# tone.net
KiCad netlist of a schematic drawn in EAGLE
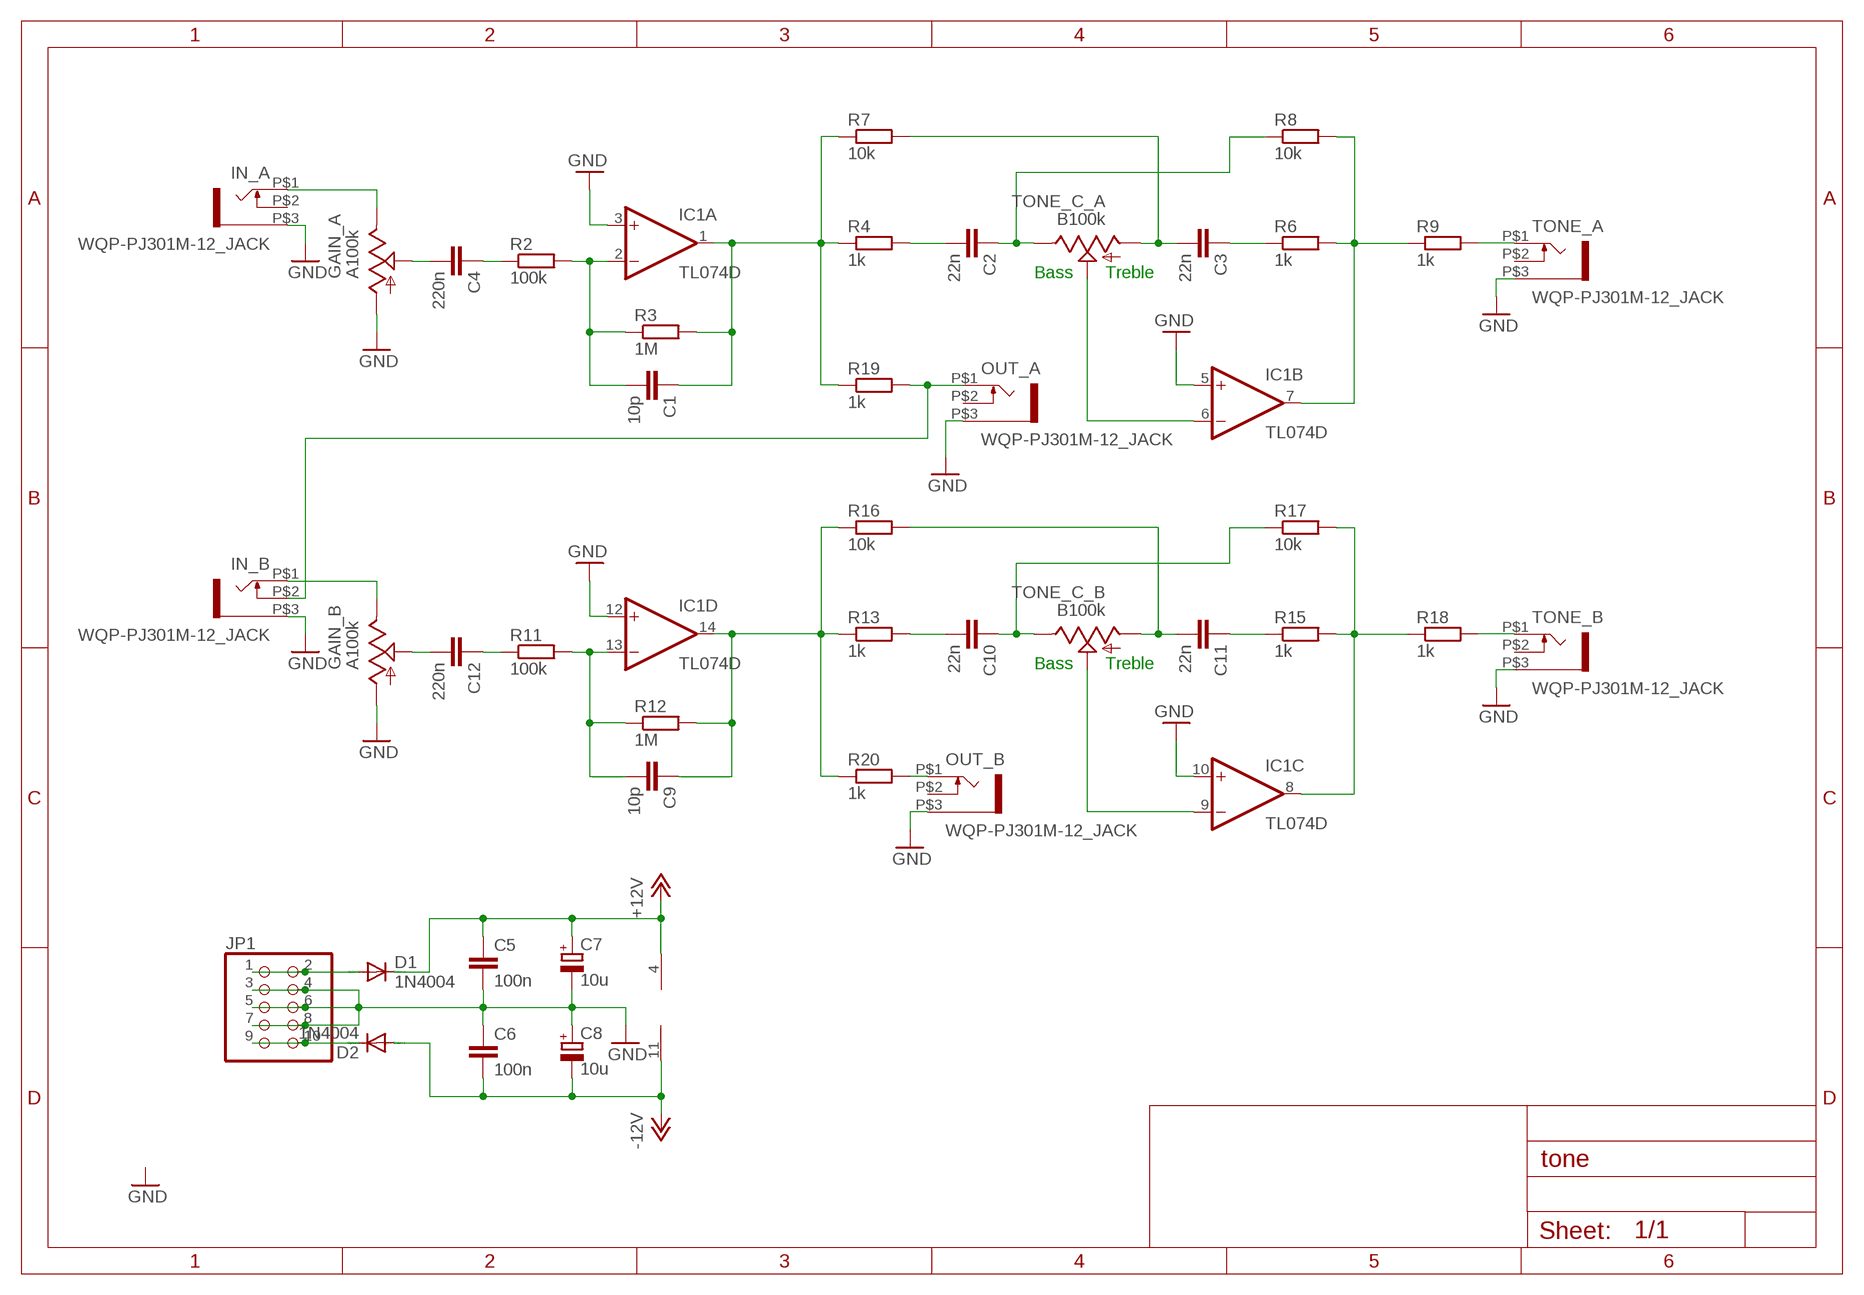
[diagram p0: schematic, sheet 1]

(export (version "E")
  (design (tool "Eeschema 10.0.6"))
  (components
    (comp (ref "C1")
      (value "10p")
      (footprint "eagle-import:C0603K")
      (libsource (lib "eagle-import") (part "C-EUC0603K"))
    )
    (comp (ref "C2")
      (value "22n")
      (footprint "eagle-import:C050-025X075")
      (libsource (lib "eagle-import") (part "C-EU050-025X075"))
    )
    (comp (ref "C3")
      (value "22n")
      (footprint "eagle-import:C050-025X075")
      (libsource (lib "eagle-import") (part "C-EU050-025X075"))
    )
    (comp (ref "C4")
      (value "220n")
      (footprint "eagle-import:C050-025X075")
      (libsource (lib "eagle-import") (part "C-EU050-025X075"))
    )
    (comp (ref "C5")
      (value "100n")
      (footprint "eagle-import:C025-025X050")
      (libsource (lib "eagle-import") (part "C-EU025-025X050"))
    )
    (comp (ref "C6")
      (value "100n")
      (footprint "eagle-import:C025-025X050")
      (libsource (lib "eagle-import") (part "C-EU025-025X050"))
    )
    (comp (ref "C7")
      (value "10u")
      (footprint "eagle-import:E2,5-6")
      (libsource (lib "eagle-import") (part "CPOL-EUE2.5-6"))
    )
    (comp (ref "C8")
      (value "10u")
      (footprint "eagle-import:E2,5-6")
      (libsource (lib "eagle-import") (part "CPOL-EUE2.5-6"))
    )
    (comp (ref "C9")
      (value "10p")
      (footprint "eagle-import:C0603K")
      (libsource (lib "eagle-import") (part "C-EUC0603K"))
    )
    (comp (ref "C10")
      (value "22n")
      (footprint "eagle-import:C050-025X075")
      (libsource (lib "eagle-import") (part "C-EU050-025X075"))
    )
    (comp (ref "C11")
      (value "22n")
      (footprint "eagle-import:C050-025X075")
      (libsource (lib "eagle-import") (part "C-EU050-025X075"))
    )
    (comp (ref "C12")
      (value "220n")
      (footprint "eagle-import:C050-025X075")
      (libsource (lib "eagle-import") (part "C-EU050-025X075"))
    )
    (comp (ref "D1")
      (value "1N4004")
      (footprint "eagle-import:DO41-10")
      (libsource (lib "eagle-import") (part "1N4004"))
    )
    (comp (ref "D2")
      (value "1N4004")
      (footprint "eagle-import:DO41-10")
      (libsource (lib "eagle-import") (part "1N4004"))
    )
    (comp (ref "GAIN_A")
      (value "A100k")
      (footprint "eagle-import:ALPS_POT_VERTICAL")
      (libsource (lib "eagle-import") (part "POT_USVERTICAL"))
    )
    (comp (ref "GAIN_B")
      (value "A100k")
      (footprint "eagle-import:ALPS_POT_VERTICAL")
      (libsource (lib "eagle-import") (part "POT_USVERTICAL"))
    )
    (comp (ref "IC1")
      (value "TL074D")
      (footprint "eagle-import:SO14")
      (libsource (lib "eagle-import") (part "TL074D"))
    )
    (comp (ref "IN_A")
      (value "WQP-PJ301M-12_JACK")
      (footprint "eagle-import:WQP-PJ301M-12_JACK")
      (libsource (lib "eagle-import") (part "WQP-PJ301M-12_JACK"))
    )
    (comp (ref "IN_B")
      (value "WQP-PJ301M-12_JACK")
      (footprint "eagle-import:WQP-PJ301M-12_JACK")
      (libsource (lib "eagle-import") (part "WQP-PJ301M-12_JACK"))
    )
    (comp (ref "JP1")
      (value "PINHD-2X5")
      (footprint "eagle-import:2X05")
      (libsource (lib "eagle-import") (part "PINHD-2X5"))
    )
    (comp (ref "OUT_A")
      (value "WQP-PJ301M-12_JACK")
      (footprint "eagle-import:WQP-PJ301M-12_JACK")
      (libsource (lib "eagle-import") (part "WQP-PJ301M-12_JACK"))
    )
    (comp (ref "OUT_B")
      (value "WQP-PJ301M-12_JACK")
      (footprint "eagle-import:WQP-PJ301M-12_JACK")
      (libsource (lib "eagle-import") (part "WQP-PJ301M-12_JACK"))
    )
    (comp (ref "R2")
      (value "100k")
      (footprint "eagle-import:R0603")
      (libsource (lib "eagle-import") (part "R-EU_R0603"))
    )
    (comp (ref "R3")
      (value "1M")
      (footprint "eagle-import:R0603")
      (libsource (lib "eagle-import") (part "R-EU_R0603"))
    )
    (comp (ref "R4")
      (value "1k")
      (footprint "eagle-import:R0603")
      (libsource (lib "eagle-import") (part "R-EU_R0603"))
    )
    (comp (ref "R6")
      (value "1k")
      (footprint "eagle-import:R0603")
      (libsource (lib "eagle-import") (part "R-EU_R0603"))
    )
    (comp (ref "R7")
      (value "10k")
      (footprint "eagle-import:R0603")
      (libsource (lib "eagle-import") (part "R-EU_R0603"))
    )
    (comp (ref "R8")
      (value "10k")
      (footprint "eagle-import:R0603")
      (libsource (lib "eagle-import") (part "R-EU_R0603"))
    )
    (comp (ref "R9")
      (value "1k")
      (footprint "eagle-import:R0603")
      (libsource (lib "eagle-import") (part "R-EU_R0603"))
    )
    (comp (ref "R11")
      (value "100k")
      (footprint "eagle-import:R0603")
      (libsource (lib "eagle-import") (part "R-EU_R0603"))
    )
    (comp (ref "R12")
      (value "1M")
      (footprint "eagle-import:R0603")
      (libsource (lib "eagle-import") (part "R-EU_R0603"))
    )
    (comp (ref "R13")
      (value "1k")
      (footprint "eagle-import:R0603")
      (libsource (lib "eagle-import") (part "R-EU_R0603"))
    )
    (comp (ref "R15")
      (value "1k")
      (footprint "eagle-import:R0603")
      (libsource (lib "eagle-import") (part "R-EU_R0603"))
    )
    (comp (ref "R16")
      (value "10k")
      (footprint "eagle-import:R0603")
      (libsource (lib "eagle-import") (part "R-EU_R0603"))
    )
    (comp (ref "R17")
      (value "10k")
      (footprint "eagle-import:R0603")
      (libsource (lib "eagle-import") (part "R-EU_R0603"))
    )
    (comp (ref "R18")
      (value "1k")
      (footprint "eagle-import:R0603")
      (libsource (lib "eagle-import") (part "R-EU_R0603"))
    )
    (comp (ref "R19")
      (value "1k")
      (footprint "eagle-import:R0603")
      (libsource (lib "eagle-import") (part "R-EU_R0603"))
    )
    (comp (ref "R20")
      (value "1k")
      (footprint "eagle-import:R0603")
      (libsource (lib "eagle-import") (part "R-EU_R0603"))
    )
    (comp (ref "TONE_A")
      (value "WQP-PJ301M-12_JACK")
      (footprint "eagle-import:WQP-PJ301M-12_JACK")
      (libsource (lib "eagle-import") (part "WQP-PJ301M-12_JACK"))
    )
    (comp (ref "TONE_B")
      (value "WQP-PJ301M-12_JACK")
      (footprint "eagle-import:WQP-PJ301M-12_JACK")
      (libsource (lib "eagle-import") (part "WQP-PJ301M-12_JACK"))
    )
    (comp (ref "TONE_C_A")
      (value "B100k")
      (footprint "eagle-import:ALPS_POT_VERTICAL")
      (libsource (lib "eagle-import") (part "POT_USVERTICAL"))
    )
    (comp (ref "TONE_C_B")
      (value "B100k")
      (footprint "eagle-import:ALPS_POT_VERTICAL")
      (libsource (lib "eagle-import") (part "POT_USVERTICAL"))
    )
  )
  (nets
    (net (code "1") (name "+12V") (class "Default")
      (node (ref "C5") (pin "1") (pinfunction "1_1") (pintype "passive"))
      (node (ref "C7") (pin "+") (pinfunction "+_+") (pintype "passive"))
      (node (ref "D1") (pin "C") (pinfunction "C_C") (pintype "passive"))
      (node (ref "IC1") (pin "4") (pinfunction "V+_4") (pintype "power_in"))
    )
    (net (code "2") (name "-12V") (class "Default")
      (node (ref "C6") (pin "2") (pinfunction "2_2") (pintype "passive"))
      (node (ref "C8") (pin "-") (pinfunction "-_-") (pintype "passive"))
      (node (ref "D2") (pin "A") (pinfunction "A_A") (pintype "passive"))
      (node (ref "IC1") (pin "11") (pinfunction "V-_11") (pintype "power_in"))
    )
    (net (code "3") (name "GND") (class "Default")
      (node (ref "C5") (pin "2") (pinfunction "2_2") (pintype "passive"))
      (node (ref "C6") (pin "1") (pinfunction "1_1") (pintype "passive"))
      (node (ref "C7") (pin "-") (pinfunction "-_-") (pintype "passive"))
      (node (ref "C8") (pin "+") (pinfunction "+_+") (pintype "passive"))
      (node (ref "GAIN_A") (pin "P$3") (pinfunction "A_P$3") (pintype "passive"))
      (node (ref "GAIN_B") (pin "P$3") (pinfunction "A_P$3") (pintype "passive"))
      (node (ref "IC1") (pin "10") (pinfunction "+IN_10") (pintype "input"))
      (node (ref "IC1") (pin "12") (pinfunction "+IN_12") (pintype "input"))
      (node (ref "IC1") (pin "3") (pinfunction "+IN_3") (pintype "input"))
      (node (ref "IC1") (pin "5") (pinfunction "+IN_5") (pintype "input"))
      (node (ref "IN_A") (pin "P$3") (pinfunction "1_P$3") (pintype "passive"))
      (node (ref "IN_B") (pin "P$3") (pinfunction "1_P$3") (pintype "passive"))
      (node (ref "JP1") (pin "3") (pinfunction "3_3") (pintype "passive"))
      (node (ref "JP1") (pin "4") (pinfunction "4_4") (pintype "passive"))
      (node (ref "JP1") (pin "5") (pinfunction "5_5") (pintype "passive"))
      (node (ref "JP1") (pin "6") (pinfunction "6_6") (pintype "passive"))
      (node (ref "JP1") (pin "7") (pinfunction "7_7") (pintype "passive"))
      (node (ref "JP1") (pin "8") (pinfunction "8_8") (pintype "passive"))
      (node (ref "OUT_A") (pin "P$3") (pinfunction "1_P$3") (pintype "passive"))
      (node (ref "OUT_B") (pin "P$3") (pinfunction "1_P$3") (pintype "passive"))
      (node (ref "TONE_A") (pin "P$3") (pinfunction "1_P$3") (pintype "passive"))
      (node (ref "TONE_B") (pin "P$3") (pinfunction "1_P$3") (pintype "passive"))
    )
    (net (code "4") (name "Net-(C2-Pad2)") (class "Default")
      (node (ref "C2") (pin "2") (pinfunction "2_2") (pintype "passive"))
      (node (ref "R4") (pin "2") (pinfunction "2_2") (pintype "passive"))
    )
    (net (code "5") (name "Net-(C3-Pad1)") (class "Default")
      (node (ref "C3") (pin "1") (pinfunction "1_1") (pintype "passive"))
      (node (ref "R6") (pin "1") (pinfunction "1_1") (pintype "passive"))
    )
    (net (code "6") (name "Net-(C4-Pad1)") (class "Default")
      (node (ref "C4") (pin "1") (pinfunction "1_1") (pintype "passive"))
      (node (ref "R2") (pin "1") (pinfunction "1_1") (pintype "passive"))
    )
    (net (code "7") (name "Net-(C10-Pad2)") (class "Default")
      (node (ref "C10") (pin "2") (pinfunction "2_2") (pintype "passive"))
      (node (ref "R13") (pin "2") (pinfunction "2_2") (pintype "passive"))
    )
    (net (code "8") (name "Net-(C11-Pad1)") (class "Default")
      (node (ref "C11") (pin "1") (pinfunction "1_1") (pintype "passive"))
      (node (ref "R15") (pin "1") (pinfunction "1_1") (pintype "passive"))
    )
    (net (code "9") (name "Net-(C12-Pad1)") (class "Default")
      (node (ref "C12") (pin "1") (pinfunction "1_1") (pintype "passive"))
      (node (ref "R11") (pin "1") (pinfunction "1_1") (pintype "passive"))
    )
    (net (code "10") (name "Net-(D1-PadA)") (class "Default")
      (node (ref "D1") (pin "A") (pinfunction "A_A") (pintype "passive"))
      (node (ref "JP1") (pin "1") (pinfunction "1_1") (pintype "passive"))
      (node (ref "JP1") (pin "2") (pinfunction "2_2") (pintype "passive"))
    )
    (net (code "11") (name "Net-(D2-PadC)") (class "Default")
      (node (ref "D2") (pin "C") (pinfunction "C_C") (pintype "passive"))
      (node (ref "JP1") (pin "10") (pinfunction "10_10") (pintype "passive"))
      (node (ref "JP1") (pin "9") (pinfunction "9_9") (pintype "passive"))
    )
    (net (code "12") (name "Net-(GAIN_A-E)") (class "Default")
      (node (ref "GAIN_A") (pin "P$1") (pinfunction "E_P$1") (pintype "passive"))
      (node (ref "IN_A") (pin "P$1") (pinfunction "2_P$1") (pintype "passive"))
    )
    (net (code "13") (name "Net-(GAIN_A-S)") (class "Default")
      (node (ref "C4") (pin "2") (pinfunction "2_2") (pintype "passive"))
      (node (ref "GAIN_A") (pin "P$2") (pinfunction "S_P$2") (pintype "passive"))
    )
    (net (code "14") (name "Net-(GAIN_B-E)") (class "Default")
      (node (ref "GAIN_B") (pin "P$1") (pinfunction "E_P$1") (pintype "passive"))
      (node (ref "IN_B") (pin "P$1") (pinfunction "2_P$1") (pintype "passive"))
    )
    (net (code "15") (name "Net-(GAIN_B-S)") (class "Default")
      (node (ref "C12") (pin "2") (pinfunction "2_2") (pintype "passive"))
      (node (ref "GAIN_B") (pin "P$2") (pinfunction "S_P$2") (pintype "passive"))
    )
    (net (code "16") (name "Net-(IC1A--IN)") (class "Default")
      (node (ref "C1") (pin "2") (pinfunction "2_2") (pintype "passive"))
      (node (ref "IC1") (pin "2") (pinfunction "-IN_2") (pintype "input"))
      (node (ref "R2") (pin "2") (pinfunction "2_2") (pintype "passive"))
      (node (ref "R3") (pin "1") (pinfunction "1_1") (pintype "passive"))
    )
    (net (code "17") (name "Net-(IC1A-OUT)") (class "Default")
      (node (ref "C1") (pin "1") (pinfunction "1_1") (pintype "passive"))
      (node (ref "IC1") (pin "1") (pinfunction "OUT_1") (pintype "output"))
      (node (ref "R19") (pin "1") (pinfunction "1_1") (pintype "passive"))
      (node (ref "R3") (pin "2") (pinfunction "2_2") (pintype "passive"))
      (node (ref "R4") (pin "1") (pinfunction "1_1") (pintype "passive"))
      (node (ref "R7") (pin "1") (pinfunction "1_1") (pintype "passive"))
    )
    (net (code "18") (name "Net-(IC1B--IN)") (class "Default")
      (node (ref "IC1") (pin "6") (pinfunction "-IN_6") (pintype "input"))
      (node (ref "TONE_C_A") (pin "P$2") (pinfunction "S_P$2") (pintype "passive"))
    )
    (net (code "19") (name "Net-(IC1B-OUT)") (class "Default")
      (node (ref "IC1") (pin "7") (pinfunction "OUT_7") (pintype "output"))
      (node (ref "R6") (pin "2") (pinfunction "2_2") (pintype "passive"))
      (node (ref "R8") (pin "2") (pinfunction "2_2") (pintype "passive"))
      (node (ref "R9") (pin "1") (pinfunction "1_1") (pintype "passive"))
    )
    (net (code "20") (name "Net-(IC1C--IN)") (class "Default")
      (node (ref "IC1") (pin "9") (pinfunction "-IN_9") (pintype "input"))
      (node (ref "TONE_C_B") (pin "P$2") (pinfunction "S_P$2") (pintype "passive"))
    )
    (net (code "21") (name "Net-(IC1C-OUT)") (class "Default")
      (node (ref "IC1") (pin "8") (pinfunction "OUT_8") (pintype "output"))
      (node (ref "R15") (pin "2") (pinfunction "2_2") (pintype "passive"))
      (node (ref "R17") (pin "2") (pinfunction "2_2") (pintype "passive"))
      (node (ref "R18") (pin "1") (pinfunction "1_1") (pintype "passive"))
    )
    (net (code "22") (name "Net-(IC1D--IN)") (class "Default")
      (node (ref "C9") (pin "2") (pinfunction "2_2") (pintype "passive"))
      (node (ref "IC1") (pin "13") (pinfunction "-IN_13") (pintype "input"))
      (node (ref "R11") (pin "2") (pinfunction "2_2") (pintype "passive"))
      (node (ref "R12") (pin "1") (pinfunction "1_1") (pintype "passive"))
    )
    (net (code "23") (name "Net-(IC1D-OUT)") (class "Default")
      (node (ref "C9") (pin "1") (pinfunction "1_1") (pintype "passive"))
      (node (ref "IC1") (pin "14") (pinfunction "OUT_14") (pintype "output"))
      (node (ref "R12") (pin "2") (pinfunction "2_2") (pintype "passive"))
      (node (ref "R13") (pin "1") (pinfunction "1_1") (pintype "passive"))
      (node (ref "R16") (pin "1") (pinfunction "1_1") (pintype "passive"))
      (node (ref "R20") (pin "1") (pinfunction "1_1") (pintype "passive"))
    )
    (net (code "24") (name "Net-(IN_B-3)") (class "Default")
      (node (ref "IN_B") (pin "P$2") (pinfunction "3_P$2") (pintype "passive"))
      (node (ref "OUT_A") (pin "P$1") (pinfunction "2_P$1") (pintype "passive"))
      (node (ref "R19") (pin "2") (pinfunction "2_2") (pintype "passive"))
    )
    (net (code "25") (name "Net-(OUT_B-2)") (class "Default")
      (node (ref "OUT_B") (pin "P$1") (pinfunction "2_P$1") (pintype "passive"))
      (node (ref "R20") (pin "2") (pinfunction "2_2") (pintype "passive"))
    )
    (net (code "26") (name "Net-(TONE_A-2)") (class "Default")
      (node (ref "R9") (pin "2") (pinfunction "2_2") (pintype "passive"))
      (node (ref "TONE_A") (pin "P$1") (pinfunction "2_P$1") (pintype "passive"))
    )
    (net (code "27") (name "Net-(TONE_B-2)") (class "Default")
      (node (ref "R18") (pin "2") (pinfunction "2_2") (pintype "passive"))
      (node (ref "TONE_B") (pin "P$1") (pinfunction "2_P$1") (pintype "passive"))
    )
    (net (code "28") (name "Net-(TONE_C_A-A)") (class "Default")
      (node (ref "C3") (pin "2") (pinfunction "2_2") (pintype "passive"))
      (node (ref "R7") (pin "2") (pinfunction "2_2") (pintype "passive"))
      (node (ref "TONE_C_A") (pin "P$3") (pinfunction "A_P$3") (pintype "passive"))
    )
    (net (code "29") (name "Net-(TONE_C_A-E)") (class "Default")
      (node (ref "C2") (pin "1") (pinfunction "1_1") (pintype "passive"))
      (node (ref "R8") (pin "1") (pinfunction "1_1") (pintype "passive"))
      (node (ref "TONE_C_A") (pin "P$1") (pinfunction "E_P$1") (pintype "passive"))
    )
    (net (code "30") (name "Net-(TONE_C_B-A)") (class "Default")
      (node (ref "C11") (pin "2") (pinfunction "2_2") (pintype "passive"))
      (node (ref "R16") (pin "2") (pinfunction "2_2") (pintype "passive"))
      (node (ref "TONE_C_B") (pin "P$3") (pinfunction "A_P$3") (pintype "passive"))
    )
    (net (code "31") (name "Net-(TONE_C_B-E)") (class "Default")
      (node (ref "C10") (pin "1") (pinfunction "1_1") (pintype "passive"))
      (node (ref "R17") (pin "1") (pinfunction "1_1") (pintype "passive"))
      (node (ref "TONE_C_B") (pin "P$1") (pinfunction "E_P$1") (pintype "passive"))
    )
    (net (code "32") (name "unconnected-(IN_A-3-PadP$2)") (class "Default")
      (node (ref "IN_A") (pin "P$2") (pinfunction "3_P$2") (pintype "passive"))
    )
    (net (code "33") (name "unconnected-(OUT_A-3-PadP$2)") (class "Default")
      (node (ref "OUT_A") (pin "P$2") (pinfunction "3_P$2") (pintype "passive"))
    )
    (net (code "34") (name "unconnected-(OUT_B-3-PadP$2)") (class "Default")
      (node (ref "OUT_B") (pin "P$2") (pinfunction "3_P$2") (pintype "passive"))
    )
    (net (code "35") (name "unconnected-(TONE_A-3-PadP$2)") (class "Default")
      (node (ref "TONE_A") (pin "P$2") (pinfunction "3_P$2") (pintype "passive"))
    )
    (net (code "36") (name "unconnected-(TONE_B-3-PadP$2)") (class "Default")
      (node (ref "TONE_B") (pin "P$2") (pinfunction "3_P$2") (pintype "passive"))
    )
  )
)
